# B.net
KiCad netlist of a schematic drawn in Altium Designer
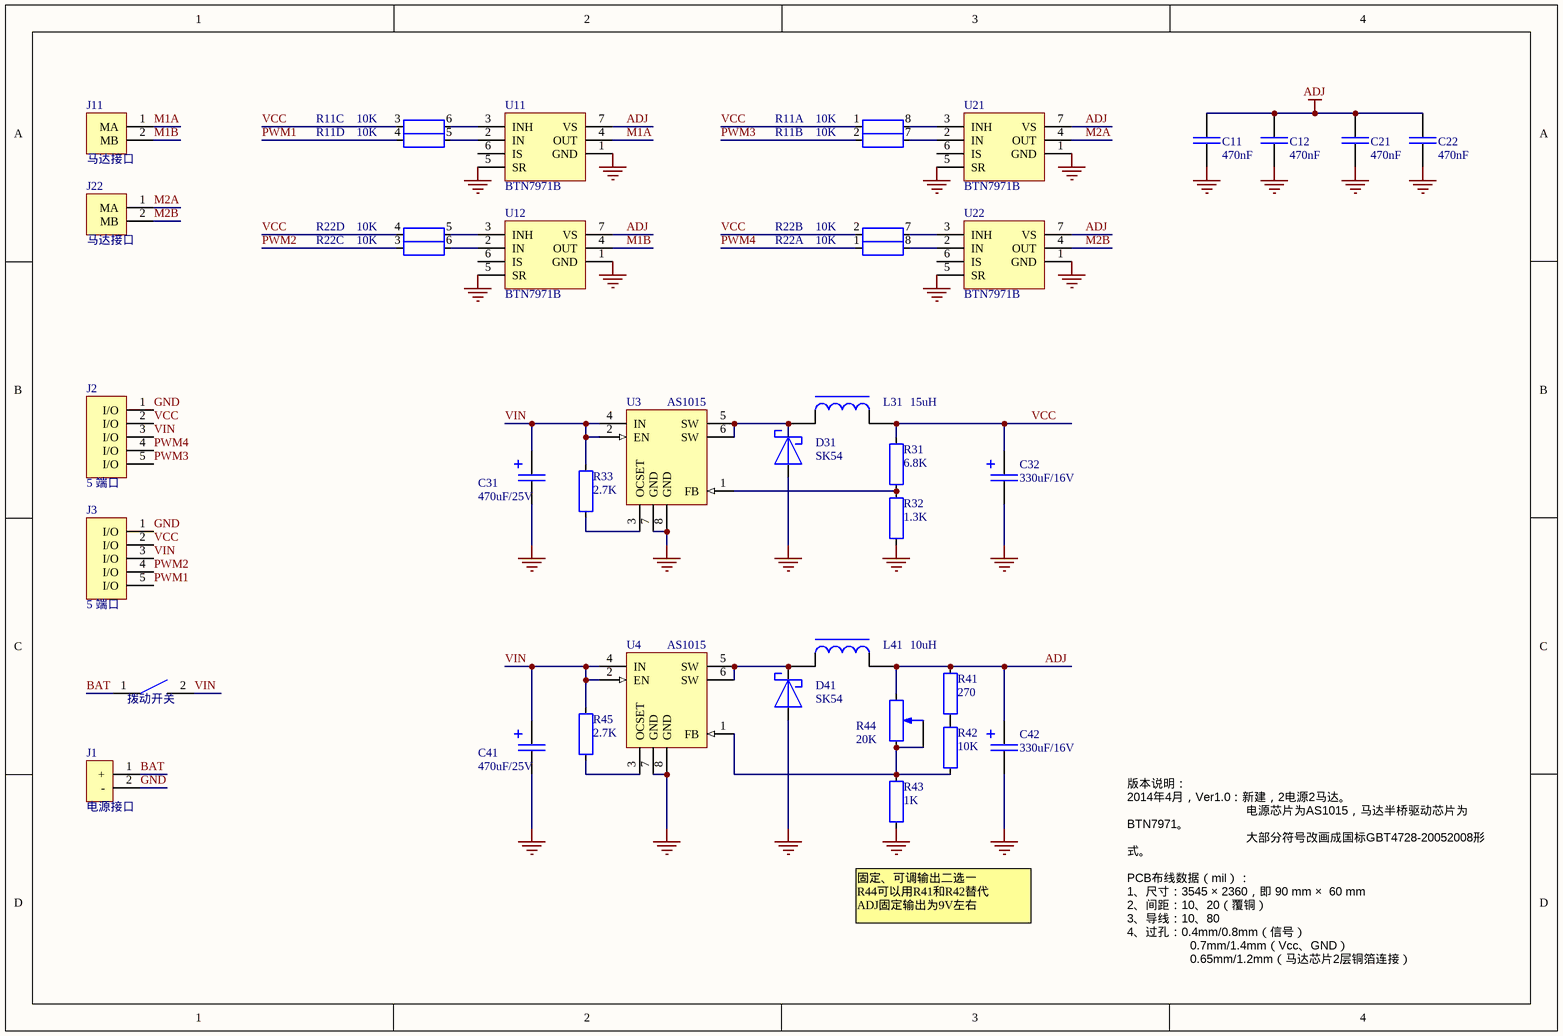
[diagram p0: B.SchDoc]

(export (version "E")
  (design (tool "Eeschema 10.0.6"))
  (components
    (comp (ref "C11") (value "470nF") (footprint "0805") (libsource (lib "RC") (part "C")))
    (comp (ref "C12") (value "470nF") (footprint "0805") (libsource (lib "RC") (part "C")))
    (comp (ref "C21") (value "470nF") (footprint "0805") (libsource (lib "RC") (part "C")))
    (comp (ref "C22") (value "470nF") (footprint "0805") (libsource (lib "RC") (part "C")))
    (comp (ref "C31") (value "470uF/25V") (libsource (lib "RC") (part "C+")))
    (comp (ref "C32") (value "330uF/16V") (libsource (lib "RC") (part "C+")))
    (comp (ref "C41") (value "470uF/25V") (libsource (lib "RC") (part "C+")))
    (comp (ref "C42") (value "330uF/16V") (libsource (lib "RC") (part "C+")))
    (comp (ref "D31") (value "SK54") (footprint "SMC/DO-214AB") (libsource (lib "RC") (part "D")))
    (comp (ref "D41") (value "SK54") (footprint "SMC/DO-214AB") (libsource (lib "RC") (part "D")))
    (comp (ref "J1") (value "电源接口") (footprint "DC12V") (libsource (lib "RC") (part "电源接口")))
    (comp (ref "J2") (value "5 端口") (footprint "SIP5") (libsource (lib "RC") (part "5 端口")))
    (comp (ref "J3") (value "5 端口") (footprint "SIP5") (libsource (lib "RC") (part "5 端口")))
    (comp (ref "J11") (value "马达接口") (footprint "MOTOR-W") (libsource (lib "RC") (part "马达接口")))
    (comp (ref "J22") (value "马达接口") (footprint "MOTOR-W") (libsource (lib "RC") (part "马达接口")))
    (comp (ref "L31") (value "15uH") (footprint "4040电感") (libsource (lib "RC") (part "L")))
    (comp (ref "L41") (value "10uH") (footprint "4040电感") (libsource (lib "RC") (part "L")))
    (comp (ref "R11")
      (value "10K")
      (footprint "PZ-4")
      (description "Isolated Resistor Network - Parts")
      (libsource (lib "RC") (part "Res Pack"))
    )
    (comp (ref "R22")
      (value "10K")
      (footprint "PZ-4")
      (description "Isolated Resistor Network - Parts")
      (libsource (lib "RC") (part "Res Pack"))
    )
    (comp (ref "R31") (value "6.8K") (footprint "0805") (libsource (lib "RC") (part "R")))
    (comp (ref "R32") (value "1.3K") (footprint "0805") (libsource (lib "RC") (part "R")))
    (comp (ref "R33") (value "2.7K") (footprint "0805") (libsource (lib "RC") (part "R")))
    (comp (ref "R41") (value "270") (footprint "0805") (libsource (lib "RC") (part "R")))
    (comp (ref "R42") (value "10K") (footprint "0805") (libsource (lib "RC") (part "R")))
    (comp (ref "R43") (value "1K") (footprint "0805") (libsource (lib "RC") (part "R")))
    (comp (ref "R44")
      (value "20K")
      (footprint "电位器")
      (description "Potentiometer")
      (libsource (lib "RC") (part "可变电阻"))
    )
    (comp (ref "R45") (value "2.7K") (footprint "0805") (libsource (lib "RC") (part "R")))
    (comp (ref "U3") (value "AS1015") (footprint "SOP8_M") (libsource (lib "RC") (part "AS1015")))
    (comp (ref "U4") (value "AS1015") (footprint "SOP8_M") (libsource (lib "RC") (part "AS1015")))
    (comp (ref "U11") (value "BTN7971B") (footprint "TO263-7-1") (libsource (lib "RC") (part "BTN7971B")))
    (comp (ref "U12") (value "BTN7971B") (footprint "TO263-7-1") (libsource (lib "RC") (part "BTN7971B")))
    (comp (ref "U21") (value "BTN7971B") (footprint "TO263-7-1") (libsource (lib "RC") (part "BTN7971B")))
    (comp (ref "U22") (value "BTN7971B") (footprint "TO263-7-1") (libsource (lib "RC") (part "BTN7971B")))
    (comp (ref "拨动开关")
      (value "开关")
      (footprint "5A120V开关")
      (fields (field (name "PUBLISHER") "Altium Limited"))
      (libsource (lib "RC") (part "开关"))
    )
  )
  (nets
    (net (code "1") (name "/BAT") (class "Default")
      (node (ref "J1") (pin "1") (pinfunction "+_1") (pintype "passive"))
      (node (ref "拨动开关") (pin "1") (pinfunction "1_1") (pintype "passive"))
    )
    (net (code "2") (name "/M1A") (class "Default")
      (node (ref "J11") (pin "1") (pinfunction "MA_1") (pintype "passive"))
      (node (ref "U11") (pin "4") (pinfunction "OUT_4") (pintype "passive"))
    )
    (net (code "3") (name "/M1B") (class "Default")
      (node (ref "J11") (pin "2") (pinfunction "MB_2") (pintype "passive"))
      (node (ref "U12") (pin "4") (pinfunction "OUT_4") (pintype "passive"))
    )
    (net (code "4") (name "/M2A") (class "Default")
      (node (ref "J22") (pin "1") (pinfunction "MA_1") (pintype "passive"))
      (node (ref "U21") (pin "4") (pinfunction "OUT_4") (pintype "passive"))
    )
    (net (code "5") (name "/M2B") (class "Default")
      (node (ref "J22") (pin "2") (pinfunction "MB_2") (pintype "passive"))
      (node (ref "U22") (pin "4") (pinfunction "OUT_4") (pintype "passive"))
    )
    (net (code "6") (name "/PWM1") (class "Default")
      (node (ref "J3") (pin "5") (pinfunction "I/O_5") (pintype "passive"))
      (node (ref "R11") (pin "4") (pinfunction "4_4") (pintype "passive"))
    )
    (net (code "7") (name "/PWM2") (class "Default")
      (node (ref "J3") (pin "4") (pinfunction "I/O_4") (pintype "passive"))
      (node (ref "R22") (pin "3") (pinfunction "3_3") (pintype "passive"))
    )
    (net (code "8") (name "/PWM3") (class "Default")
      (node (ref "J2") (pin "5") (pinfunction "I/O_5") (pintype "passive"))
      (node (ref "R11") (pin "2") (pinfunction "2_2") (pintype "passive"))
    )
    (net (code "9") (name "/PWM4") (class "Default")
      (node (ref "J2") (pin "4") (pinfunction "I/O_4") (pintype "passive"))
      (node (ref "R22") (pin "1") (pinfunction "1_1") (pintype "passive"))
    )
    (net (code "10") (name "/VCC") (class "Default")
      (node (ref "C32") (pin "1") (pinfunction "1_1") (pintype "passive"))
      (node (ref "J2") (pin "2") (pinfunction "I/O_2") (pintype "passive"))
      (node (ref "J3") (pin "2") (pinfunction "I/O_2") (pintype "passive"))
      (node (ref "L31") (pin "2") (pinfunction "2_2") (pintype "passive"))
      (node (ref "R11") (pin "1") (pinfunction "1_1") (pintype "passive"))
      (node (ref "R11") (pin "3") (pinfunction "3_3") (pintype "passive"))
      (node (ref "R22") (pin "2") (pinfunction "2_2") (pintype "passive"))
      (node (ref "R22") (pin "4") (pinfunction "4_4") (pintype "passive"))
      (node (ref "R31") (pin "2") (pinfunction "2_2") (pintype "passive"))
    )
    (net (code "11") (name "/VIN") (class "Default")
      (node (ref "C31") (pin "1") (pinfunction "1_1") (pintype "passive"))
      (node (ref "C41") (pin "1") (pinfunction "1_1") (pintype "passive"))
      (node (ref "J2") (pin "3") (pinfunction "I/O_3") (pintype "passive"))
      (node (ref "J3") (pin "3") (pinfunction "I/O_3") (pintype "passive"))
      (node (ref "R33") (pin "2") (pinfunction "2_2") (pintype "passive"))
      (node (ref "R45") (pin "2") (pinfunction "2_2") (pintype "passive"))
      (node (ref "U3") (pin "2") (pinfunction "EN_2") (pintype "input"))
      (node (ref "U3") (pin "4") (pinfunction "IN_4") (pintype "power_in"))
      (node (ref "U4") (pin "2") (pinfunction "EN_2") (pintype "input"))
      (node (ref "U4") (pin "4") (pinfunction "IN_4") (pintype "power_in"))
      (node (ref "拨动开关") (pin "2") (pinfunction "2_2") (pintype "passive"))
    )
    (net (code "12") (name "ADJ") (class "Default")
      (node (ref "C11") (pin "2") (pinfunction "2_2") (pintype "passive"))
      (node (ref "C12") (pin "2") (pinfunction "2_2") (pintype "passive"))
      (node (ref "C21") (pin "1") (pinfunction "1_1") (pintype "passive"))
      (node (ref "C22") (pin "1") (pinfunction "1_1") (pintype "passive"))
      (node (ref "C42") (pin "1") (pinfunction "1_1") (pintype "passive"))
      (node (ref "L41") (pin "2") (pinfunction "2_2") (pintype "passive"))
      (node (ref "R41") (pin "2") (pinfunction "2_2") (pintype "passive"))
      (node (ref "R44") (pin "1") (pinfunction "1_1") (pintype "passive"))
      (node (ref "U11") (pin "7") (pinfunction "VS_7") (pintype "passive"))
      (node (ref "U12") (pin "7") (pinfunction "VS_7") (pintype "passive"))
      (node (ref "U21") (pin "7") (pinfunction "VS_7") (pintype "passive"))
      (node (ref "U22") (pin "7") (pinfunction "VS_7") (pintype "passive"))
    )
    (net (code "13") (name "GND") (class "Default")
      (node (ref "C11") (pin "1") (pinfunction "1_1") (pintype "passive"))
      (node (ref "C12") (pin "1") (pinfunction "1_1") (pintype "passive"))
      (node (ref "C21") (pin "2") (pinfunction "2_2") (pintype "passive"))
      (node (ref "C22") (pin "2") (pinfunction "2_2") (pintype "passive"))
      (node (ref "C31") (pin "2") (pinfunction "2_2") (pintype "passive"))
      (node (ref "C32") (pin "2") (pinfunction "2_2") (pintype "passive"))
      (node (ref "C41") (pin "2") (pinfunction "2_2") (pintype "passive"))
      (node (ref "C42") (pin "2") (pinfunction "2_2") (pintype "passive"))
      (node (ref "D31") (pin "1") (pinfunction "A_1") (pintype "passive"))
      (node (ref "D41") (pin "1") (pinfunction "A_1") (pintype "passive"))
      (node (ref "J1") (pin "2") (pinfunction "-_2") (pintype "passive"))
      (node (ref "J2") (pin "1") (pinfunction "I/O_1") (pintype "passive"))
      (node (ref "J3") (pin "1") (pinfunction "I/O_1") (pintype "passive"))
      (node (ref "R32") (pin "1") (pinfunction "1_1") (pintype "passive"))
      (node (ref "R43") (pin "1") (pinfunction "1_1") (pintype "passive"))
      (node (ref "U11") (pin "1") (pinfunction "GND_1") (pintype "passive"))
      (node (ref "U11") (pin "5") (pinfunction "SR_5") (pintype "passive"))
      (node (ref "U12") (pin "1") (pinfunction "GND_1") (pintype "passive"))
      (node (ref "U12") (pin "5") (pinfunction "SR_5") (pintype "passive"))
      (node (ref "U21") (pin "1") (pinfunction "GND_1") (pintype "passive"))
      (node (ref "U21") (pin "5") (pinfunction "SR_5") (pintype "passive"))
      (node (ref "U22") (pin "1") (pinfunction "GND_1") (pintype "passive"))
      (node (ref "U22") (pin "5") (pinfunction "SR_5") (pintype "passive"))
      (node (ref "U3") (pin "7") (pinfunction "GND_7") (pintype "passive"))
      (node (ref "U3") (pin "8") (pinfunction "GND_8") (pintype "passive"))
      (node (ref "U4") (pin "7") (pinfunction "GND_7") (pintype "passive"))
      (node (ref "U4") (pin "8") (pinfunction "GND_8") (pintype "passive"))
    )
    (net (code "14") (name "Net-(D31-K)") (class "Default")
      (node (ref "D31") (pin "2") (pinfunction "K_2") (pintype "passive"))
      (node (ref "L31") (pin "1") (pinfunction "1_1") (pintype "passive"))
      (node (ref "U3") (pin "5") (pinfunction "SW_5") (pintype "power_in"))
      (node (ref "U3") (pin "6") (pinfunction "SW_6") (pintype "power_in"))
    )
    (net (code "15") (name "Net-(D41-K)") (class "Default")
      (node (ref "D41") (pin "2") (pinfunction "K_2") (pintype "passive"))
      (node (ref "L41") (pin "1") (pinfunction "1_1") (pintype "passive"))
      (node (ref "U4") (pin "5") (pinfunction "SW_5") (pintype "power_in"))
      (node (ref "U4") (pin "6") (pinfunction "SW_6") (pintype "power_in"))
    )
    (net (code "16") (name "Net-(R41-Pad1)") (class "Default")
      (node (ref "R41") (pin "1") (pinfunction "1_1") (pintype "passive"))
      (node (ref "R42") (pin "2") (pinfunction "2_2") (pintype "passive"))
    )
    (net (code "17") (name "Net-(U3-FB)") (class "Default")
      (node (ref "R31") (pin "1") (pinfunction "1_1") (pintype "passive"))
      (node (ref "R32") (pin "2") (pinfunction "2_2") (pintype "passive"))
      (node (ref "U3") (pin "1") (pinfunction "FB_1") (pintype "input"))
    )
    (net (code "18") (name "Net-(U3-OCSET)") (class "Default")
      (node (ref "R33") (pin "1") (pinfunction "1_1") (pintype "passive"))
      (node (ref "U3") (pin "3") (pinfunction "OCSET_3") (pintype "power_in"))
    )
    (net (code "19") (name "Net-(U4-FB)") (class "Default")
      (node (ref "R42") (pin "1") (pinfunction "1_1") (pintype "passive"))
      (node (ref "R43") (pin "2") (pinfunction "2_2") (pintype "passive"))
      (node (ref "R44") (pin "2") (pinfunction "2_2") (pintype "passive"))
      (node (ref "R44") (pin "3") (pinfunction "3_3") (pintype "passive"))
      (node (ref "U4") (pin "1") (pinfunction "FB_1") (pintype "input"))
    )
    (net (code "20") (name "Net-(U4-OCSET)") (class "Default")
      (node (ref "R45") (pin "1") (pinfunction "1_1") (pintype "passive"))
      (node (ref "U4") (pin "3") (pinfunction "OCSET_3") (pintype "power_in"))
    )
    (net (code "21") (name "Net-(U11-IN)") (class "Default")
      (node (ref "R11") (pin "5") (pinfunction "5_5") (pintype "passive"))
      (node (ref "U11") (pin "2") (pinfunction "IN_2") (pintype "passive"))
    )
    (net (code "22") (name "Net-(U11-INH)") (class "Default")
      (node (ref "R11") (pin "6") (pinfunction "6_6") (pintype "passive"))
      (node (ref "U11") (pin "3") (pinfunction "INH_3") (pintype "passive"))
    )
    (net (code "23") (name "Net-(U12-IN)") (class "Default")
      (node (ref "R22") (pin "6") (pinfunction "6_6") (pintype "passive"))
      (node (ref "U12") (pin "2") (pinfunction "IN_2") (pintype "passive"))
    )
    (net (code "24") (name "Net-(U12-INH)") (class "Default")
      (node (ref "R22") (pin "5") (pinfunction "5_5") (pintype "passive"))
      (node (ref "U12") (pin "3") (pinfunction "INH_3") (pintype "passive"))
    )
    (net (code "25") (name "Net-(U21-IN)") (class "Default")
      (node (ref "R11") (pin "7") (pinfunction "7_7") (pintype "passive"))
      (node (ref "U21") (pin "2") (pinfunction "IN_2") (pintype "passive"))
    )
    (net (code "26") (name "Net-(U21-INH)") (class "Default")
      (node (ref "R11") (pin "8") (pinfunction "8_8") (pintype "passive"))
      (node (ref "U21") (pin "3") (pinfunction "INH_3") (pintype "passive"))
    )
    (net (code "27") (name "Net-(U22-IN)") (class "Default")
      (node (ref "R22") (pin "8") (pinfunction "8_8") (pintype "passive"))
      (node (ref "U22") (pin "2") (pinfunction "IN_2") (pintype "passive"))
    )
    (net (code "28") (name "Net-(U22-INH)") (class "Default")
      (node (ref "R22") (pin "7") (pinfunction "7_7") (pintype "passive"))
      (node (ref "U22") (pin "3") (pinfunction "INH_3") (pintype "passive"))
    )
    (net (code "29") (name "unconnected-(U11-IS-Pad6)") (class "Default")
      (node (ref "U11") (pin "6") (pinfunction "IS_6") (pintype "passive"))
    )
    (net (code "30") (name "unconnected-(U12-IS-Pad6)") (class "Default")
      (node (ref "U12") (pin "6") (pinfunction "IS_6") (pintype "passive"))
    )
    (net (code "31") (name "unconnected-(U21-IS-Pad6)") (class "Default")
      (node (ref "U21") (pin "6") (pinfunction "IS_6") (pintype "passive"))
    )
    (net (code "32") (name "unconnected-(U22-IS-Pad6)") (class "Default")
      (node (ref "U22") (pin "6") (pinfunction "IS_6") (pintype "passive"))
    )
  )
)
